# 02_Power.net
KiCad netlist of a schematic drawn in Altium Designer
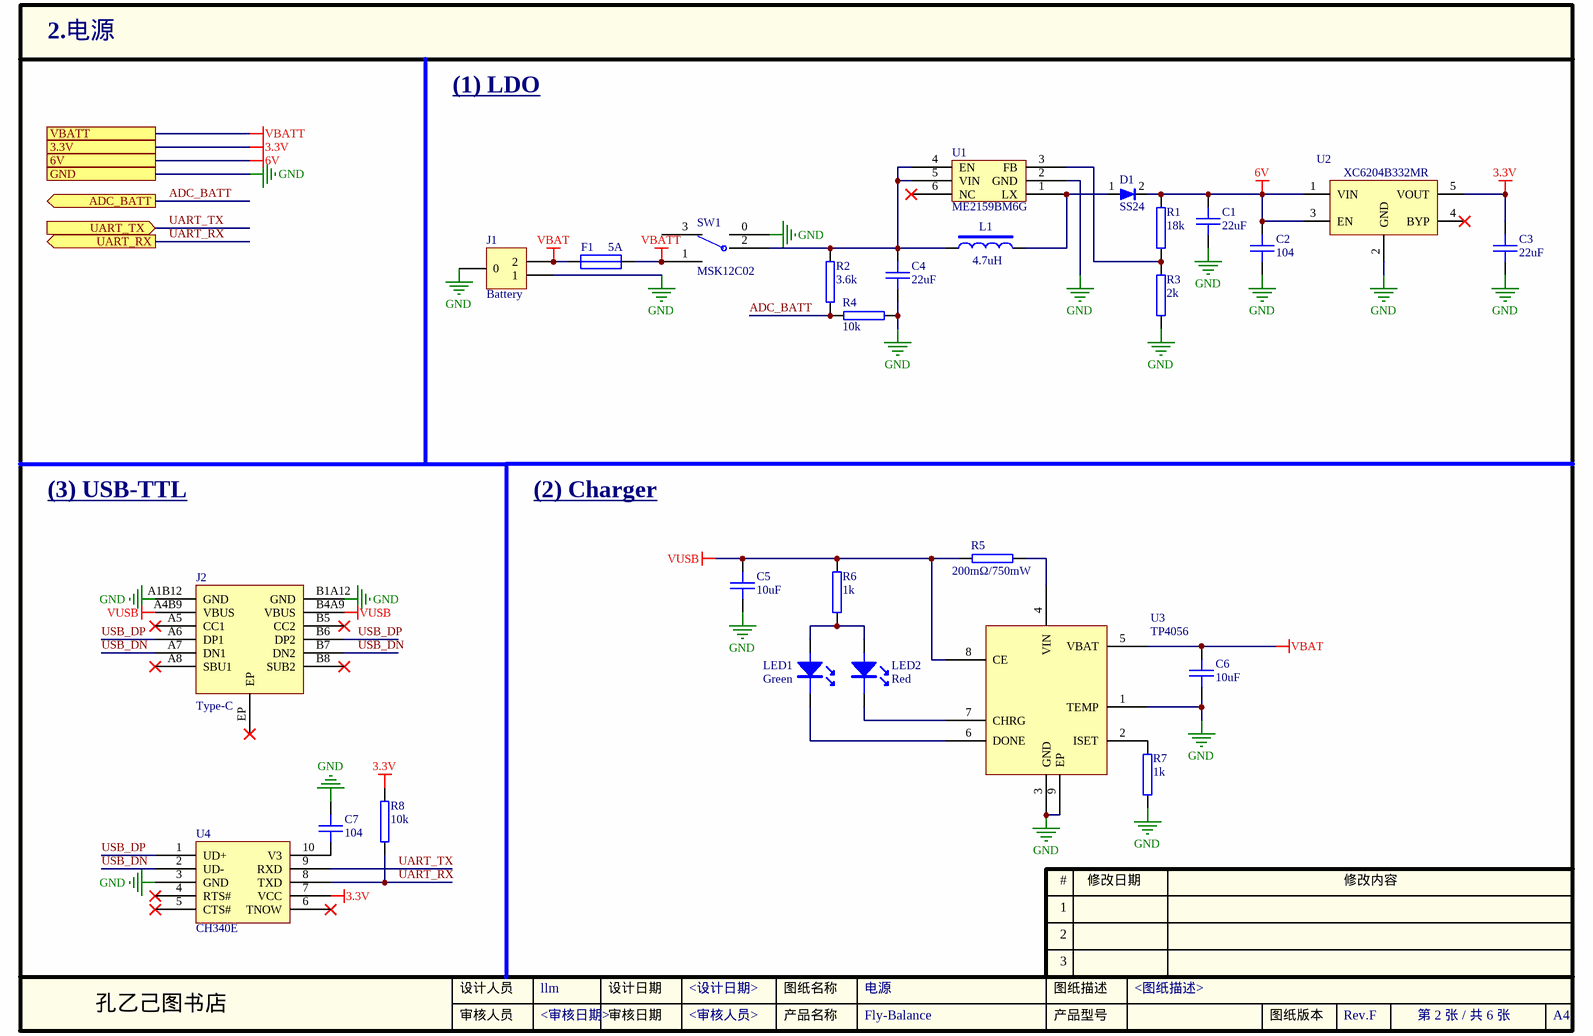
[diagram p0: 02_Power.SchDoc]

(export (version "E")
  (design (tool "Eeschema 10.0.6"))
  (components
    (comp (ref "C1")
      (value "22uF")
      (footprint "0805C")
      (description "电容")
      (libsource (lib "MY_Schlib") (part "CAP"))
    )
    (comp (ref "C2")
      (value "104")
      (footprint "0402C")
      (description "电容")
      (libsource (lib "MY_Schlib") (part "CAP"))
    )
    (comp (ref "C3")
      (value "22uF")
      (footprint "0805C")
      (description "电容")
      (libsource (lib "MY_Schlib") (part "CAP"))
    )
    (comp (ref "C4")
      (value "22uF")
      (footprint "0805C")
      (description "电容")
      (libsource (lib "MY_Schlib") (part "CAP"))
    )
    (comp (ref "C5")
      (value "10uF")
      (footprint "0805C")
      (description "电容")
      (libsource (lib "MY_Schlib") (part "CAP"))
    )
    (comp (ref "C6")
      (value "10uF")
      (footprint "0805C")
      (description "电容")
      (libsource (lib "MY_Schlib") (part "CAP"))
    )
    (comp (ref "C7")
      (value "104")
      (footprint "0402C")
      (description "电容")
      (libsource (lib "MY_Schlib") (part "CAP"))
    )
    (comp (ref "D1")
      (value "SS24")
      (footprint "SMA_L4.3-W2.5-LS5.0-RD")
      (description "二极管")
      (libsource (lib "MY_Schlib") (part "DIODE"))
    )
    (comp (ref "F1")
      (value "5A")
      (footprint "1206R")
      (description "保险丝")
      (libsource (lib "MY_Schlib") (part "Fuse"))
    )
    (comp (ref "J1")
      (value "Battery")
      (footprint "51005母座")
      (description "直流电机接口")
      (libsource (lib "Schlib") (part "CON"))
    )
    (comp (ref "J2")
      (value "Type-C")
      (footprint "USB-C-SMD_TYPE-C-16P-1")
      (libsource (lib "MY_Schlib") (part "Type-C"))
    )
    (comp (ref "L1")
      (value "4.7uH")
      (footprint "IND-SMD_L5.0-W5.0_FNR50XXS")
      (description "电感")
      (libsource (lib "MY_Schlib") (part "INDUCTOR_2"))
    )
    (comp (ref "LED1")
      (value "Green")
      (footprint "LED-0603")
      (description "发光二极管")
      (libsource (lib "MY_Schlib") (part "LED"))
    )
    (comp (ref "LED2")
      (value "Red")
      (footprint "LED-0603")
      (description "发光二极管")
      (libsource (lib "MY_Schlib") (part "LED"))
    )
    (comp (ref "R1")
      (value "18k")
      (footprint "0402R")
      (description "电阻")
      (libsource (lib "MY_Schlib") (part "RES"))
    )
    (comp (ref "R2")
      (value "3.6k")
      (footprint "0402R")
      (description "电阻")
      (libsource (lib "MY_Schlib") (part "RES"))
    )
    (comp (ref "R3")
      (value "2k")
      (footprint "0402R")
      (description "电阻")
      (libsource (lib "MY_Schlib") (part "RES"))
    )
    (comp (ref "R4")
      (value "10k")
      (footprint "0402R")
      (description "电阻")
      (libsource (lib "MY_Schlib") (part "RES"))
    )
    (comp (ref "R5")
      (value "200mΩ/750mW")
      (footprint "2010R")
      (description "电阻")
      (libsource (lib "MY_Schlib") (part "RES"))
    )
    (comp (ref "R6")
      (value "1k")
      (footprint "0402R")
      (description "电阻")
      (libsource (lib "MY_Schlib") (part "RES"))
    )
    (comp (ref "R7")
      (value "1k")
      (footprint "0402R")
      (description "电阻")
      (libsource (lib "MY_Schlib") (part "RES"))
    )
    (comp (ref "R8")
      (value "10k")
      (footprint "0402R")
      (description "电阻")
      (libsource (lib "MY_Schlib") (part "RES"))
    )
    (comp (ref "SW1") (value "MSK12C02") (footprint "MSK12C02") (libsource (lib "Schlib") (part "单刀双掷开关")))
    (comp (ref "U1")
      (value "ME2159BM6G")
      (footprint "SOT-23-6_L2.9-W1.6-P0.95-LS2.8-BR")
      (description "DC-DC升压芯片")
      (libsource (lib "MY_Schlib") (part "ME2159BM6G"))
    )
    (comp (ref "U2")
      (value "XC6204B332MR")
      (footprint "SOT-23-5")
      (description "LDO, 3.0V输出")
      (libsource (lib "MY_Schlib") (part "ZL6205A30TS5"))
    )
    (comp (ref "U3")
      (value "TP4056")
      (footprint "ESOP-8_L4.9-W3.9-P1.27-LS6.0-BL-EP")
      (description "单节锂电池充电芯片")
      (libsource (lib "MY_Schlib") (part "4056"))
    )
    (comp (ref "U4")
      (value "CH340E")
      (footprint "MSOP-10_L3.0-W3.0-P0.50-LS5.0-BL")
      (description "USB-TTL芯片")
      (libsource (lib "MY_Schlib") (part "CH340E"))
    )
  )
  (nets
    (net (code "1") (name "/ADC_BATT") (class "Default")
      (node (ref "R2") (pin "1") (pinfunction "1_1") (pintype "passive"))
      (node (ref "R4") (pin "2") (pinfunction "2_2") (pintype "passive"))
    )
    (net (code "2") (name "/UART_RX") (class "Default")
      (node (ref "R8") (pin "1") (pinfunction "1_1") (pintype "passive"))
      (node (ref "U4") (pin "8") (pinfunction "TXD_8") (pintype "passive"))
    )
    (net (code "3") (name "/UART_TX") (class "Default")
      (node (ref "U4") (pin "9") (pinfunction "RXD_9") (pintype "passive"))
    )
    (net (code "4") (name "/USB_DN") (class "Default")
      (node (ref "J2") (pin "A7") (pinfunction "DN1_A7") (pintype "passive"))
      (node (ref "J2") (pin "B7") (pinfunction "DN2_B7") (pintype "passive"))
      (node (ref "U4") (pin "2") (pinfunction "UD-_2") (pintype "passive"))
    )
    (net (code "5") (name "/USB_DP") (class "Default")
      (node (ref "J2") (pin "A6") (pinfunction "DP1_A6") (pintype "passive"))
      (node (ref "J2") (pin "B6") (pinfunction "DP2_B6") (pintype "passive"))
      (node (ref "U4") (pin "1") (pinfunction "UD+_1") (pintype "passive"))
    )
    (net (code "6") (name "3.3V") (class "Default")
      (node (ref "C3") (pin "1") (pinfunction "1_1") (pintype "passive"))
      (node (ref "R8") (pin "2") (pinfunction "2_2") (pintype "passive"))
      (node (ref "U2") (pin "5") (pinfunction "VOUT_5") (pintype "passive"))
      (node (ref "U4") (pin "7") (pinfunction "VCC_7") (pintype "passive"))
    )
    (net (code "7") (name "6V") (class "Default")
      (node (ref "C1") (pin "1") (pinfunction "1_1") (pintype "passive"))
      (node (ref "C2") (pin "1") (pinfunction "1_1") (pintype "passive"))
      (node (ref "D1") (pin "2") (pinfunction "2_2") (pintype "passive"))
      (node (ref "R1") (pin "2") (pinfunction "2_2") (pintype "passive"))
      (node (ref "U2") (pin "1") (pinfunction "VIN_1") (pintype "passive"))
      (node (ref "U2") (pin "3") (pinfunction "EN_3") (pintype "passive"))
    )
    (net (code "8") (name "GND") (class "Default")
      (node (ref "C1") (pin "2") (pinfunction "2_2") (pintype "passive"))
      (node (ref "C2") (pin "2") (pinfunction "2_2") (pintype "passive"))
      (node (ref "C3") (pin "2") (pinfunction "2_2") (pintype "passive"))
      (node (ref "C4") (pin "2") (pinfunction "2_2") (pintype "passive"))
      (node (ref "C5") (pin "2") (pinfunction "2_2") (pintype "passive"))
      (node (ref "C6") (pin "2") (pinfunction "2_2") (pintype "passive"))
      (node (ref "C7") (pin "2") (pinfunction "2_2") (pintype "passive"))
      (node (ref "J1") (pin "0") (pinfunction "0_0") (pintype "passive"))
      (node (ref "J1") (pin "1") (pinfunction "1_1") (pintype "passive"))
      (node (ref "J2") (pin "A1B12") (pinfunction "GND_A1B12") (pintype "passive"))
      (node (ref "J2") (pin "B1A12") (pinfunction "GND_B1A12") (pintype "passive"))
      (node (ref "R3") (pin "1") (pinfunction "1_1") (pintype "passive"))
      (node (ref "R4") (pin "1") (pinfunction "1_1") (pintype "passive"))
      (node (ref "R7") (pin "1") (pinfunction "1_1") (pintype "passive"))
      (node (ref "SW1") (pin "0") (pinfunction "0_0") (pintype "power_in"))
      (node (ref "U1") (pin "2") (pinfunction "GND_2") (pintype "passive"))
      (node (ref "U2") (pin "2") (pinfunction "GND_2") (pintype "passive"))
      (node (ref "U3") (pin "1") (pinfunction "TEMP_1") (pintype "passive"))
      (node (ref "U3") (pin "3") (pinfunction "GND_3") (pintype "passive"))
      (node (ref "U3") (pin "9") (pinfunction "EP_9") (pintype "passive"))
      (node (ref "U4") (pin "3") (pinfunction "GND_3") (pintype "passive"))
    )
    (net (code "9") (name "Net-(LED1-Pad1)") (class "Default")
      (node (ref "LED1") (pin "1") (pinfunction "1_1") (pintype "passive"))
      (node (ref "LED2") (pin "1") (pinfunction "1_1") (pintype "passive"))
      (node (ref "R6") (pin "1") (pinfunction "1_1") (pintype "passive"))
    )
    (net (code "10") (name "Net-(U1-EN)") (class "Default")
      (node (ref "C4") (pin "1") (pinfunction "1_1") (pintype "passive"))
      (node (ref "L1") (pin "1") (pinfunction "1_1") (pintype "passive"))
      (node (ref "R2") (pin "2") (pinfunction "2_2") (pintype "passive"))
      (node (ref "SW1") (pin "2") (pinfunction "2_2") (pintype "power_in"))
      (node (ref "U1") (pin "4") (pinfunction "EN_4") (pintype "passive"))
      (node (ref "U1") (pin "5") (pinfunction "VIN_5") (pintype "passive"))
    )
    (net (code "11") (name "Net-(U1-FB)") (class "Default")
      (node (ref "R1") (pin "1") (pinfunction "1_1") (pintype "passive"))
      (node (ref "R3") (pin "2") (pinfunction "2_2") (pintype "passive"))
      (node (ref "U1") (pin "3") (pinfunction "FB_3") (pintype "passive"))
    )
    (net (code "12") (name "Net-(U1-LX)") (class "Default")
      (node (ref "D1") (pin "1") (pinfunction "1_1") (pintype "passive"))
      (node (ref "L1") (pin "2") (pinfunction "2_2") (pintype "passive"))
      (node (ref "U1") (pin "1") (pinfunction "LX_1") (pintype "passive"))
    )
    (net (code "13") (name "Net-(U3-CHRG)") (class "Default")
      (node (ref "LED2") (pin "2") (pinfunction "2_2") (pintype "passive"))
      (node (ref "U3") (pin "7") (pinfunction "CHRG_7") (pintype "passive"))
    )
    (net (code "14") (name "Net-(U3-DONE)") (class "Default")
      (node (ref "LED1") (pin "2") (pinfunction "2_2") (pintype "passive"))
      (node (ref "U3") (pin "6") (pinfunction "DONE_6") (pintype "passive"))
    )
    (net (code "15") (name "Net-(U3-ISET)") (class "Default")
      (node (ref "R7") (pin "2") (pinfunction "2_2") (pintype "passive"))
      (node (ref "U3") (pin "2") (pinfunction "ISET_2") (pintype "passive"))
    )
    (net (code "16") (name "Net-(U3-VIN)") (class "Default")
      (node (ref "R5") (pin "1") (pinfunction "1_1") (pintype "passive"))
      (node (ref "U3") (pin "4") (pinfunction "VIN_4") (pintype "passive"))
    )
    (net (code "17") (name "Net-(U4-V3)") (class "Default")
      (node (ref "C7") (pin "1") (pinfunction "1_1") (pintype "passive"))
      (node (ref "U4") (pin "10") (pinfunction "V3_10") (pintype "passive"))
    )
    (net (code "18") (name "VBAT") (class "Default")
      (node (ref "C6") (pin "1") (pinfunction "1_1") (pintype "passive"))
      (node (ref "F1") (pin "2") (pinfunction "2_2") (pintype "passive"))
      (node (ref "J1") (pin "2") (pinfunction "2_2") (pintype "passive"))
      (node (ref "U3") (pin "5") (pinfunction "VBAT_5") (pintype "passive"))
    )
    (net (code "19") (name "VBATT") (class "Default")
      (node (ref "F1") (pin "1") (pinfunction "1_1") (pintype "passive"))
      (node (ref "SW1") (pin "1") (pinfunction "1_1") (pintype "power_in"))
    )
    (net (code "20") (name "VUSB") (class "Default")
      (node (ref "C5") (pin "1") (pinfunction "1_1") (pintype "passive"))
      (node (ref "J2") (pin "A4B9") (pinfunction "VBUS_A4B9") (pintype "passive"))
      (node (ref "J2") (pin "B4A9") (pinfunction "VBUS_B4A9") (pintype "passive"))
      (node (ref "R5") (pin "2") (pinfunction "2_2") (pintype "passive"))
      (node (ref "R6") (pin "2") (pinfunction "2_2") (pintype "passive"))
      (node (ref "U3") (pin "8") (pinfunction "CE_8") (pintype "passive"))
    )
    (net (code "21") (name "unconnected-(J2-CC1-PadA5)") (class "Default")
      (node (ref "J2") (pin "A5") (pinfunction "CC1_A5") (pintype "passive+no_connect"))
    )
    (net (code "22") (name "unconnected-(J2-CC2-PadB5)") (class "Default")
      (node (ref "J2") (pin "B5") (pinfunction "CC2_B5") (pintype "passive+no_connect"))
    )
    (net (code "23") (name "unconnected-(J2-PadEP)") (class "Default")
      (node (ref "J2") (pin "EP") (pinfunction "EP_EP") (pintype "passive+no_connect"))
    )
    (net (code "24") (name "unconnected-(J2-SBU1-PadA8)") (class "Default")
      (node (ref "J2") (pin "A8") (pinfunction "SBU1_A8") (pintype "passive+no_connect"))
    )
    (net (code "25") (name "unconnected-(J2-SUB2-PadB8)") (class "Default")
      (node (ref "J2") (pin "B8") (pinfunction "SUB2_B8") (pintype "passive+no_connect"))
    )
    (net (code "26") (name "unconnected-(SW1-Pad3)") (class "Default")
      (node (ref "SW1") (pin "3") (pinfunction "3_3") (pintype "power_in"))
    )
    (net (code "27") (name "unconnected-(U1-NC-Pad6)") (class "Default")
      (node (ref "U1") (pin "6") (pinfunction "NC_6") (pintype "passive+no_connect"))
    )
    (net (code "28") (name "unconnected-(U2-BYP-Pad4)") (class "Default")
      (node (ref "U2") (pin "4") (pinfunction "BYP_4") (pintype "passive+no_connect"))
    )
    (net (code "29") (name "unconnected-(U4-CTS#-Pad5)") (class "Default")
      (node (ref "U4") (pin "5") (pinfunction "CTS#_5") (pintype "passive+no_connect"))
    )
    (net (code "30") (name "unconnected-(U4-RTS#-Pad4)") (class "Default")
      (node (ref "U4") (pin "4") (pinfunction "RTS#_4") (pintype "passive+no_connect"))
    )
    (net (code "31") (name "unconnected-(U4-TNOW-Pad6)") (class "Default")
      (node (ref "U4") (pin "6") (pinfunction "TNOW_6") (pintype "passive+no_connect"))
    )
  )
)
